# Motor_Drivers.net
KiCad netlist of a schematic drawn in Altium Designer
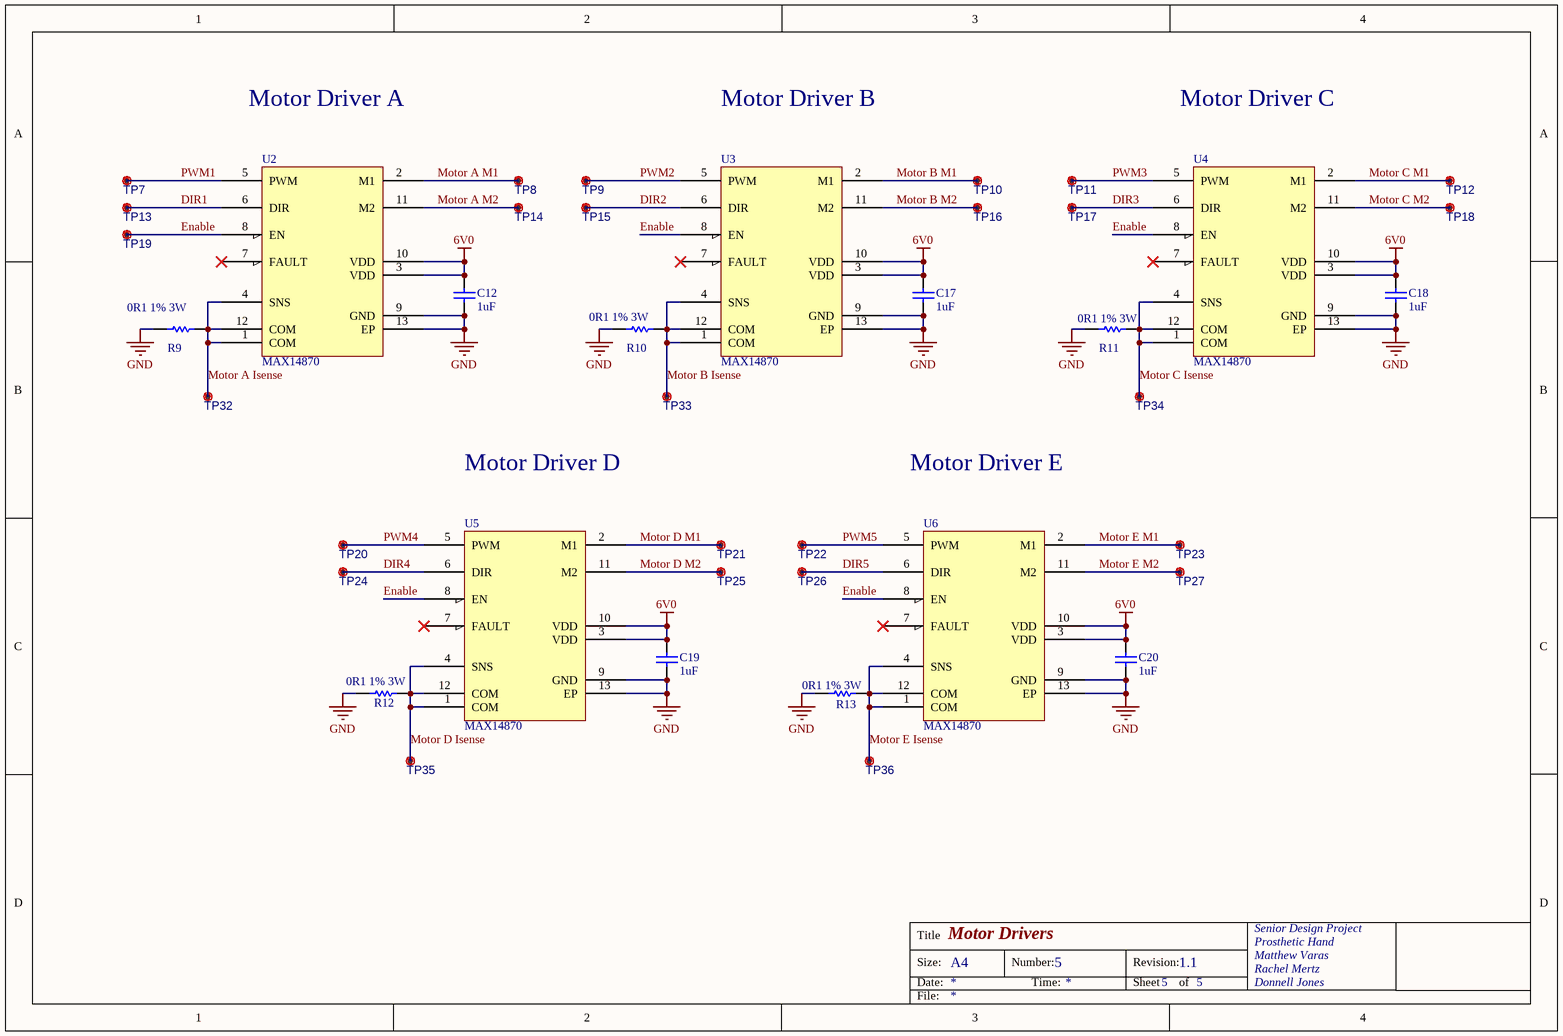
[diagram p0: Motor_Drivers.SchDoc]

(export (version "E")
  (design (tool "Eeschema 10.0.6"))
  (components
    (comp (ref "C12")
      (value "1uF")
      (footprint "CAPC0402(1005)60_N")
      (description "CAP CER 1UF 16V X5R 0402")
      (fields (field (name "TOLERANCE") "Â±10%"))
      (libsource (lib "Altium Content Vault") (part "CMP-1034-02119-1"))
    )
    (comp (ref "C17")
      (value "1uF")
      (footprint "CAPC0402(1005)60_N")
      (description "CAP CER 1UF 16V X5R 0402")
      (fields (field (name "TOLERANCE") "Â±10%"))
      (libsource (lib "Altium Content Vault") (part "CMP-1034-02119-1"))
    )
    (comp (ref "C18")
      (value "1uF")
      (footprint "CAPC0402(1005)60_N")
      (description "CAP CER 1UF 16V X5R 0402")
      (fields (field (name "TOLERANCE") "Â±10%"))
      (libsource (lib "Altium Content Vault") (part "CMP-1034-02119-1"))
    )
    (comp (ref "C19")
      (value "1uF")
      (footprint "CAPC0402(1005)60_N")
      (description "CAP CER 1UF 16V X5R 0402")
      (fields (field (name "TOLERANCE") "Â±10%"))
      (libsource (lib "Altium Content Vault") (part "CMP-1034-02119-1"))
    )
    (comp (ref "C20")
      (value "1uF")
      (footprint "CAPC0402(1005)60_N")
      (description "CAP CER 1UF 16V X5R 0402")
      (fields (field (name "TOLERANCE") "Â±10%"))
      (libsource (lib "Altium Content Vault") (part "CMP-1034-02119-1"))
    )
    (comp (ref "R9")
      (value "0R1 1% 3W")
      (footprint "RESC2512(6432)_N")
      (description "RES SMD 0.1 OHM 1% 3W 2512")
      (fields (field (name "POWER") "3W") (field (name "TOLERANCE") "1%"))
      (libsource (lib "Altium Content Vault") (part "CMP-1018-00002-1"))
    )
    (comp (ref "R10")
      (value "0R1 1% 3W")
      (footprint "RESC2512(6432)_N")
      (description "RES SMD 0.1 OHM 1% 3W 2512")
      (fields (field (name "POWER") "3W") (field (name "TOLERANCE") "1%"))
      (libsource (lib "Altium Content Vault") (part "CMP-1018-00002-1"))
    )
    (comp (ref "R11")
      (value "0R1 1% 3W")
      (footprint "RESC2512(6432)_N")
      (description "RES SMD 0.1 OHM 1% 3W 2512")
      (fields (field (name "POWER") "3W") (field (name "TOLERANCE") "1%"))
      (libsource (lib "Altium Content Vault") (part "CMP-1018-00002-1"))
    )
    (comp (ref "R12")
      (value "0R1 1% 3W")
      (footprint "RESC2512(6432)_N")
      (description "RES SMD 0.1 OHM 1% 3W 2512")
      (fields (field (name "POWER") "3W") (field (name "TOLERANCE") "1%"))
      (libsource (lib "Altium Content Vault") (part "CMP-1018-00002-1"))
    )
    (comp (ref "R13")
      (value "0R1 1% 3W")
      (footprint "RESC2512(6432)_N")
      (description "RES SMD 0.1 OHM 1% 3W 2512")
      (fields (field (name "POWER") "3W") (field (name "TOLERANCE") "1%"))
      (libsource (lib "Altium Content Vault") (part "CMP-1018-00002-1"))
    )
    (comp (ref "TP7")
      (value "Test Point")
      (footprint "Testpoint_70")
      (description "Test Pad")
      (libsource (lib "Prosthetic Hand Schematic Lib") (part "Test Point"))
    )
    (comp (ref "TP8")
      (value "Test Point")
      (footprint "Testpoint_70")
      (description "Test Pad")
      (libsource (lib "Prosthetic Hand Schematic Lib") (part "Test Point"))
    )
    (comp (ref "TP9")
      (value "Test Point")
      (footprint "Testpoint_70")
      (description "Test Pad")
      (libsource (lib "Prosthetic Hand Schematic Lib") (part "Test Point"))
    )
    (comp (ref "TP10")
      (value "Test Point")
      (footprint "Testpoint_70")
      (description "Test Pad")
      (libsource (lib "Prosthetic Hand Schematic Lib") (part "Test Point"))
    )
    (comp (ref "TP11")
      (value "Test Point")
      (footprint "Testpoint_70")
      (description "Test Pad")
      (libsource (lib "Prosthetic Hand Schematic Lib") (part "Test Point"))
    )
    (comp (ref "TP12")
      (value "Test Point")
      (footprint "Testpoint_70")
      (description "Test Pad")
      (libsource (lib "Prosthetic Hand Schematic Lib") (part "Test Point"))
    )
    (comp (ref "TP13")
      (value "Test Point")
      (footprint "Testpoint_70")
      (description "Test Pad")
      (libsource (lib "Prosthetic Hand Schematic Lib") (part "Test Point"))
    )
    (comp (ref "TP14")
      (value "Test Point")
      (footprint "Testpoint_70")
      (description "Test Pad")
      (libsource (lib "Prosthetic Hand Schematic Lib") (part "Test Point"))
    )
    (comp (ref "TP15")
      (value "Test Point")
      (footprint "Testpoint_70")
      (description "Test Pad")
      (libsource (lib "Prosthetic Hand Schematic Lib") (part "Test Point"))
    )
    (comp (ref "TP16")
      (value "Test Point")
      (footprint "Testpoint_70")
      (description "Test Pad")
      (libsource (lib "Prosthetic Hand Schematic Lib") (part "Test Point"))
    )
    (comp (ref "TP17")
      (value "Test Point")
      (footprint "Testpoint_70")
      (description "Test Pad")
      (libsource (lib "Prosthetic Hand Schematic Lib") (part "Test Point"))
    )
    (comp (ref "TP18")
      (value "Test Point")
      (footprint "Testpoint_70")
      (description "Test Pad")
      (libsource (lib "Prosthetic Hand Schematic Lib") (part "Test Point"))
    )
    (comp (ref "TP19")
      (value "Test Point")
      (footprint "Testpoint_70")
      (description "Test Pad")
      (libsource (lib "Prosthetic Hand Schematic Lib") (part "Test Point"))
    )
    (comp (ref "TP20")
      (value "Test Point")
      (footprint "Testpoint_70")
      (description "Test Pad")
      (libsource (lib "Prosthetic Hand Schematic Lib") (part "Test Point"))
    )
    (comp (ref "TP21")
      (value "Test Point")
      (footprint "Testpoint_70")
      (description "Test Pad")
      (libsource (lib "Prosthetic Hand Schematic Lib") (part "Test Point"))
    )
    (comp (ref "TP22")
      (value "Test Point")
      (footprint "Testpoint_70")
      (description "Test Pad")
      (libsource (lib "Prosthetic Hand Schematic Lib") (part "Test Point"))
    )
    (comp (ref "TP23")
      (value "Test Point")
      (footprint "Testpoint_70")
      (description "Test Pad")
      (libsource (lib "Prosthetic Hand Schematic Lib") (part "Test Point"))
    )
    (comp (ref "TP24")
      (value "Test Point")
      (footprint "Testpoint_70")
      (description "Test Pad")
      (libsource (lib "Prosthetic Hand Schematic Lib") (part "Test Point"))
    )
    (comp (ref "TP25")
      (value "Test Point")
      (footprint "Testpoint_70")
      (description "Test Pad")
      (libsource (lib "Prosthetic Hand Schematic Lib") (part "Test Point"))
    )
    (comp (ref "TP26")
      (value "Test Point")
      (footprint "Testpoint_70")
      (description "Test Pad")
      (libsource (lib "Prosthetic Hand Schematic Lib") (part "Test Point"))
    )
    (comp (ref "TP27")
      (value "Test Point")
      (footprint "Testpoint_70")
      (description "Test Pad")
      (libsource (lib "Prosthetic Hand Schematic Lib") (part "Test Point"))
    )
    (comp (ref "TP32")
      (value "Test Point")
      (footprint "Testpoint_70")
      (description "Test Pad")
      (libsource (lib "Prosthetic Hand Schematic Lib") (part "Test Point"))
    )
    (comp (ref "TP33")
      (value "Test Point")
      (footprint "Testpoint_70")
      (description "Test Pad")
      (libsource (lib "Prosthetic Hand Schematic Lib") (part "Test Point"))
    )
    (comp (ref "TP34")
      (value "Test Point")
      (footprint "Testpoint_70")
      (description "Test Pad")
      (libsource (lib "Prosthetic Hand Schematic Lib") (part "Test Point"))
    )
    (comp (ref "TP35")
      (value "Test Point")
      (footprint "Testpoint_70")
      (description "Test Pad")
      (libsource (lib "Prosthetic Hand Schematic Lib") (part "Test Point"))
    )
    (comp (ref "TP36")
      (value "Test Point")
      (footprint "Testpoint_70")
      (description "Test Pad")
      (libsource (lib "Prosthetic Hand Schematic Lib") (part "Test Point"))
    )
    (comp (ref "U2")
      (value "MAX14870")
      (footprint "12L TDFN 3x3")
      (description "IC MOTOR DVR DC FULL BR 12TDFN")
      (libsource (lib "Prosthetic Hand Schematic Lib") (part "MAX14870"))
    )
    (comp (ref "U3")
      (value "MAX14870")
      (footprint "12L TDFN 3x3")
      (description "IC MOTOR DVR DC FULL BR 12TDFN")
      (libsource (lib "Prosthetic Hand Schematic Lib") (part "MAX14870"))
    )
    (comp (ref "U4")
      (value "MAX14870")
      (footprint "12L TDFN 3x3")
      (description "IC MOTOR DVR DC FULL BR 12TDFN")
      (libsource (lib "Prosthetic Hand Schematic Lib") (part "MAX14870"))
    )
    (comp (ref "U5")
      (value "MAX14870")
      (footprint "12L TDFN 3x3")
      (description "IC MOTOR DVR DC FULL BR 12TDFN")
      (libsource (lib "Prosthetic Hand Schematic Lib") (part "MAX14870"))
    )
    (comp (ref "U6")
      (value "MAX14870")
      (footprint "12L TDFN 3x3")
      (description "IC MOTOR DVR DC FULL BR 12TDFN")
      (libsource (lib "Prosthetic Hand Schematic Lib") (part "MAX14870"))
    )
  )
  (nets
    (net (code "1") (name "/DIR1") (class "Default")
      (node (ref "TP13") (pin "1") (pinfunction "M80_1") (pintype "passive"))
      (node (ref "U2") (pin "6") (pinfunction "DIR_6") (pintype "passive"))
    )
    (net (code "2") (name "/DIR2") (class "Default")
      (node (ref "TP15") (pin "1") (pinfunction "M80_1") (pintype "passive"))
      (node (ref "U3") (pin "6") (pinfunction "DIR_6") (pintype "passive"))
    )
    (net (code "3") (name "/DIR3") (class "Default")
      (node (ref "TP17") (pin "1") (pinfunction "M80_1") (pintype "passive"))
      (node (ref "U4") (pin "6") (pinfunction "DIR_6") (pintype "passive"))
    )
    (net (code "4") (name "/DIR4") (class "Default")
      (node (ref "TP24") (pin "1") (pinfunction "M80_1") (pintype "passive"))
      (node (ref "U5") (pin "6") (pinfunction "DIR_6") (pintype "passive"))
    )
    (net (code "5") (name "/DIR5") (class "Default")
      (node (ref "TP26") (pin "1") (pinfunction "M80_1") (pintype "passive"))
      (node (ref "U6") (pin "6") (pinfunction "DIR_6") (pintype "passive"))
    )
    (net (code "6") (name "/Enable") (class "Default")
      (node (ref "TP19") (pin "1") (pinfunction "M80_1") (pintype "passive"))
      (node (ref "U2") (pin "8") (pinfunction "EN_8") (pintype "passive"))
      (node (ref "U3") (pin "8") (pinfunction "EN_8") (pintype "passive"))
      (node (ref "U4") (pin "8") (pinfunction "EN_8") (pintype "passive"))
      (node (ref "U5") (pin "8") (pinfunction "EN_8") (pintype "passive"))
      (node (ref "U6") (pin "8") (pinfunction "EN_8") (pintype "passive"))
    )
    (net (code "7") (name "/Motor A Isense") (class "Default")
      (node (ref "R9") (pin "2") (pinfunction "2_2") (pintype "passive"))
      (node (ref "TP32") (pin "1") (pinfunction "M80_1") (pintype "passive"))
      (node (ref "U2") (pin "1") (pinfunction "COM_1") (pintype "passive"))
      (node (ref "U2") (pin "12") (pinfunction "COM_12") (pintype "passive"))
      (node (ref "U2") (pin "4") (pinfunction "SNS_4") (pintype "passive"))
    )
    (net (code "8") (name "/Motor A M1") (class "Default")
      (node (ref "TP8") (pin "1") (pinfunction "M80_1") (pintype "passive"))
      (node (ref "U2") (pin "2") (pinfunction "M1_2") (pintype "passive"))
    )
    (net (code "9") (name "/Motor A M2") (class "Default")
      (node (ref "TP14") (pin "1") (pinfunction "M80_1") (pintype "passive"))
      (node (ref "U2") (pin "11") (pinfunction "M2_11") (pintype "passive"))
    )
    (net (code "10") (name "/Motor B Isense") (class "Default")
      (node (ref "R10") (pin "2") (pinfunction "2_2") (pintype "passive"))
      (node (ref "TP33") (pin "1") (pinfunction "M80_1") (pintype "passive"))
      (node (ref "U3") (pin "1") (pinfunction "COM_1") (pintype "passive"))
      (node (ref "U3") (pin "12") (pinfunction "COM_12") (pintype "passive"))
      (node (ref "U3") (pin "4") (pinfunction "SNS_4") (pintype "passive"))
    )
    (net (code "11") (name "/Motor B M1") (class "Default")
      (node (ref "TP10") (pin "1") (pinfunction "M80_1") (pintype "passive"))
      (node (ref "U3") (pin "2") (pinfunction "M1_2") (pintype "passive"))
    )
    (net (code "12") (name "/Motor B M2") (class "Default")
      (node (ref "TP16") (pin "1") (pinfunction "M80_1") (pintype "passive"))
      (node (ref "U3") (pin "11") (pinfunction "M2_11") (pintype "passive"))
    )
    (net (code "13") (name "/Motor C Isense") (class "Default")
      (node (ref "R11") (pin "2") (pinfunction "2_2") (pintype "passive"))
      (node (ref "TP34") (pin "1") (pinfunction "M80_1") (pintype "passive"))
      (node (ref "U4") (pin "1") (pinfunction "COM_1") (pintype "passive"))
      (node (ref "U4") (pin "12") (pinfunction "COM_12") (pintype "passive"))
      (node (ref "U4") (pin "4") (pinfunction "SNS_4") (pintype "passive"))
    )
    (net (code "14") (name "/Motor C M1") (class "Default")
      (node (ref "TP12") (pin "1") (pinfunction "M80_1") (pintype "passive"))
      (node (ref "U4") (pin "2") (pinfunction "M1_2") (pintype "passive"))
    )
    (net (code "15") (name "/Motor C M2") (class "Default")
      (node (ref "TP18") (pin "1") (pinfunction "M80_1") (pintype "passive"))
      (node (ref "U4") (pin "11") (pinfunction "M2_11") (pintype "passive"))
    )
    (net (code "16") (name "/Motor D Isense") (class "Default")
      (node (ref "R12") (pin "2") (pinfunction "2_2") (pintype "passive"))
      (node (ref "TP35") (pin "1") (pinfunction "M80_1") (pintype "passive"))
      (node (ref "U5") (pin "1") (pinfunction "COM_1") (pintype "passive"))
      (node (ref "U5") (pin "12") (pinfunction "COM_12") (pintype "passive"))
      (node (ref "U5") (pin "4") (pinfunction "SNS_4") (pintype "passive"))
    )
    (net (code "17") (name "/Motor D M1") (class "Default")
      (node (ref "TP21") (pin "1") (pinfunction "M80_1") (pintype "passive"))
      (node (ref "U5") (pin "2") (pinfunction "M1_2") (pintype "passive"))
    )
    (net (code "18") (name "/Motor D M2") (class "Default")
      (node (ref "TP25") (pin "1") (pinfunction "M80_1") (pintype "passive"))
      (node (ref "U5") (pin "11") (pinfunction "M2_11") (pintype "passive"))
    )
    (net (code "19") (name "/Motor E Isense") (class "Default")
      (node (ref "R13") (pin "2") (pinfunction "2_2") (pintype "passive"))
      (node (ref "TP36") (pin "1") (pinfunction "M80_1") (pintype "passive"))
      (node (ref "U6") (pin "1") (pinfunction "COM_1") (pintype "passive"))
      (node (ref "U6") (pin "12") (pinfunction "COM_12") (pintype "passive"))
      (node (ref "U6") (pin "4") (pinfunction "SNS_4") (pintype "passive"))
    )
    (net (code "20") (name "/Motor E M1") (class "Default")
      (node (ref "TP23") (pin "1") (pinfunction "M80_1") (pintype "passive"))
      (node (ref "U6") (pin "2") (pinfunction "M1_2") (pintype "passive"))
    )
    (net (code "21") (name "/Motor E M2") (class "Default")
      (node (ref "TP27") (pin "1") (pinfunction "M80_1") (pintype "passive"))
      (node (ref "U6") (pin "11") (pinfunction "M2_11") (pintype "passive"))
    )
    (net (code "22") (name "/PWM1") (class "Default")
      (node (ref "TP7") (pin "1") (pinfunction "M80_1") (pintype "passive"))
      (node (ref "U2") (pin "5") (pinfunction "PWM_5") (pintype "passive"))
    )
    (net (code "23") (name "/PWM2") (class "Default")
      (node (ref "TP9") (pin "1") (pinfunction "M80_1") (pintype "passive"))
      (node (ref "U3") (pin "5") (pinfunction "PWM_5") (pintype "passive"))
    )
    (net (code "24") (name "/PWM3") (class "Default")
      (node (ref "TP11") (pin "1") (pinfunction "M80_1") (pintype "passive"))
      (node (ref "U4") (pin "5") (pinfunction "PWM_5") (pintype "passive"))
    )
    (net (code "25") (name "/PWM4") (class "Default")
      (node (ref "TP20") (pin "1") (pinfunction "M80_1") (pintype "passive"))
      (node (ref "U5") (pin "5") (pinfunction "PWM_5") (pintype "passive"))
    )
    (net (code "26") (name "/PWM5") (class "Default")
      (node (ref "TP22") (pin "1") (pinfunction "M80_1") (pintype "passive"))
      (node (ref "U6") (pin "5") (pinfunction "PWM_5") (pintype "passive"))
    )
    (net (code "27") (name "6V0") (class "Default")
      (node (ref "C12") (pin "2") (pinfunction "2_2") (pintype "passive"))
      (node (ref "C17") (pin "2") (pinfunction "2_2") (pintype "passive"))
      (node (ref "C18") (pin "2") (pinfunction "2_2") (pintype "passive"))
      (node (ref "C19") (pin "2") (pinfunction "2_2") (pintype "passive"))
      (node (ref "C20") (pin "2") (pinfunction "2_2") (pintype "passive"))
      (node (ref "U2") (pin "10") (pinfunction "VDD_10") (pintype "passive"))
      (node (ref "U2") (pin "3") (pinfunction "VDD_3") (pintype "passive"))
      (node (ref "U3") (pin "10") (pinfunction "VDD_10") (pintype "passive"))
      (node (ref "U3") (pin "3") (pinfunction "VDD_3") (pintype "passive"))
      (node (ref "U4") (pin "10") (pinfunction "VDD_10") (pintype "passive"))
      (node (ref "U4") (pin "3") (pinfunction "VDD_3") (pintype "passive"))
      (node (ref "U5") (pin "10") (pinfunction "VDD_10") (pintype "passive"))
      (node (ref "U5") (pin "3") (pinfunction "VDD_3") (pintype "passive"))
      (node (ref "U6") (pin "10") (pinfunction "VDD_10") (pintype "passive"))
      (node (ref "U6") (pin "3") (pinfunction "VDD_3") (pintype "passive"))
    )
    (net (code "28") (name "GND") (class "Default")
      (node (ref "C12") (pin "1") (pinfunction "1_1") (pintype "passive"))
      (node (ref "C17") (pin "1") (pinfunction "1_1") (pintype "passive"))
      (node (ref "C18") (pin "1") (pinfunction "1_1") (pintype "passive"))
      (node (ref "C19") (pin "1") (pinfunction "1_1") (pintype "passive"))
      (node (ref "C20") (pin "1") (pinfunction "1_1") (pintype "passive"))
      (node (ref "R10") (pin "1") (pinfunction "1_1") (pintype "passive"))
      (node (ref "R11") (pin "1") (pinfunction "1_1") (pintype "passive"))
      (node (ref "R12") (pin "1") (pinfunction "1_1") (pintype "passive"))
      (node (ref "R13") (pin "1") (pinfunction "1_1") (pintype "passive"))
      (node (ref "R9") (pin "1") (pinfunction "1_1") (pintype "passive"))
      (node (ref "U2") (pin "13") (pinfunction "EP_13") (pintype "passive"))
      (node (ref "U2") (pin "9") (pinfunction "GND_9") (pintype "passive"))
      (node (ref "U3") (pin "13") (pinfunction "EP_13") (pintype "passive"))
      (node (ref "U3") (pin "9") (pinfunction "GND_9") (pintype "passive"))
      (node (ref "U4") (pin "13") (pinfunction "EP_13") (pintype "passive"))
      (node (ref "U4") (pin "9") (pinfunction "GND_9") (pintype "passive"))
      (node (ref "U5") (pin "13") (pinfunction "EP_13") (pintype "passive"))
      (node (ref "U5") (pin "9") (pinfunction "GND_9") (pintype "passive"))
      (node (ref "U6") (pin "13") (pinfunction "EP_13") (pintype "passive"))
      (node (ref "U6") (pin "9") (pinfunction "GND_9") (pintype "passive"))
    )
    (net (code "29") (name "unconnected-(U2-FAULT-Pad7)") (class "Default")
      (node (ref "U2") (pin "7") (pinfunction "FAULT_7") (pintype "passive+no_connect"))
    )
    (net (code "30") (name "unconnected-(U3-FAULT-Pad7)") (class "Default")
      (node (ref "U3") (pin "7") (pinfunction "FAULT_7") (pintype "passive+no_connect"))
    )
    (net (code "31") (name "unconnected-(U4-FAULT-Pad7)") (class "Default")
      (node (ref "U4") (pin "7") (pinfunction "FAULT_7") (pintype "passive+no_connect"))
    )
    (net (code "32") (name "unconnected-(U5-FAULT-Pad7)") (class "Default")
      (node (ref "U5") (pin "7") (pinfunction "FAULT_7") (pintype "passive+no_connect"))
    )
    (net (code "33") (name "unconnected-(U6-FAULT-Pad7)") (class "Default")
      (node (ref "U6") (pin "7") (pinfunction "FAULT_7") (pintype "passive+no_connect"))
    )
  )
)
